# power.net
KiCad netlist of a schematic drawn in Altium Designer
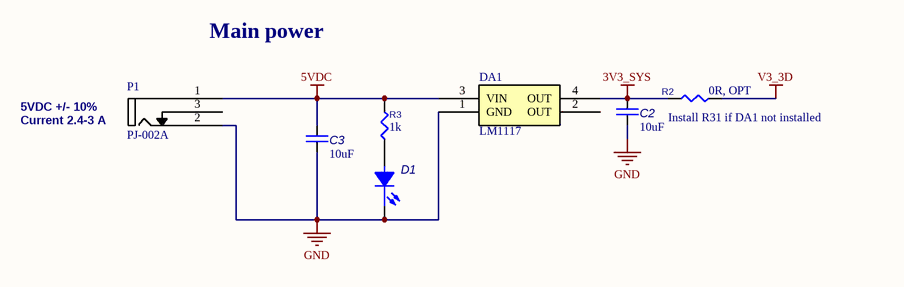
[diagram p0: power.SchDoc]

(export (version "E")
  (design (tool "Eeschema 10.0.6"))
  (components
    (comp (ref "C2")
      (value "10uF")
      (footprint "CC2012-0805")
      (description "C0805")
      (libsource (lib "am335x-base") (part "C0805"))
    )
    (comp (ref "C3")
      (value "10uF")
      (footprint "CC2012-0805")
      (description "C0805")
      (libsource (lib "am335x-base") (part "C0805"))
    )
    (comp (ref "D1")
      (value "LED0805")
      (footprint "LED0805")
      (description "LED 0805")
      (libsource (lib "spider") (part "LED0805"))
    )
    (comp (ref "DA1")
      (value "LM1117")
      (footprint "SOT230P700X160-4N")
      (description "800mA Low-Dropout Linear Regulator")
      (fields (field (name "MANUFACTURER") "National"))
      (libsource (lib "spider") (part "LM1117"))
    )
    (comp (ref "P1")
      (value "PJ-002A")
      (footprint "PJ-002A")
      (description "DC POWER JACK")
      (fields (field (name "MANUFACTURER") "CIU Inc"))
      (libsource (lib "omap") (part "PJ-002A"))
    )
    (comp (ref "R2")
      (value "0R, OPT")
      (footprint "RESC1608X55N")
      (description "R0603")
      (libsource (lib "spider") (part "R0603"))
    )
    (comp (ref "R3")
      (value "1k")
      (footprint "RESC1608X55N")
      (description "R0603")
      (libsource (lib "am335x-base") (part "R0603"))
    )
  )
  (nets
    (net (code "1") (name "3V3_SYS") (class "Default")
      (node (ref "C2") (pin "2") (pinfunction "2_2") (pintype "passive"))
      (node (ref "DA1") (pin "4") (pinfunction "OUT_4") (pintype "power_in"))
      (node (ref "R2") (pin "1") (pinfunction "1_1") (pintype "passive"))
    )
    (net (code "2") (name "5VDC") (class "Default")
      (node (ref "C3") (pin "2") (pinfunction "2_2") (pintype "passive"))
      (node (ref "DA1") (pin "3") (pinfunction "VIN_3") (pintype "power_in"))
      (node (ref "P1") (pin "1") (pinfunction "GND_1") (pintype "passive"))
      (node (ref "R3") (pin "2") (pinfunction "2_2") (pintype "passive"))
    )
    (net (code "3") (name "GND") (class "Default")
      (node (ref "C2") (pin "1") (pinfunction "1_1") (pintype "passive"))
      (node (ref "C3") (pin "1") (pinfunction "1_1") (pintype "passive"))
      (node (ref "D1") (pin "K") (pinfunction "C_K") (pintype "passive"))
      (node (ref "DA1") (pin "1") (pinfunction "GND_1") (pintype "power_in"))
      (node (ref "P1") (pin "2") (pinfunction "RIGHT_2") (pintype "passive"))
    )
    (net (code "4") (name "Net-(D1-PadA)") (class "Default")
      (node (ref "D1") (pin "A") (pinfunction "A_A") (pintype "passive"))
      (node (ref "R3") (pin "1") (pinfunction "1_1") (pintype "passive"))
    )
    (net (code "5") (name "V3_3D") (class "Default")
      (node (ref "R2") (pin "2") (pinfunction "2_2") (pintype "passive"))
    )
    (net (code "6") (name "unconnected-(DA1-OUT-Pad2)") (class "Default")
      (node (ref "DA1") (pin "2") (pinfunction "OUT_2") (pintype "power_in"))
    )
    (net (code "7") (name "unconnected-(P1-LEFT-Pad3)") (class "Default")
      (node (ref "P1") (pin "3") (pinfunction "LEFT_3") (pintype "passive"))
    )
  )
)
